# task5_eagle.net
KiCad netlist of a schematic drawn in EAGLE
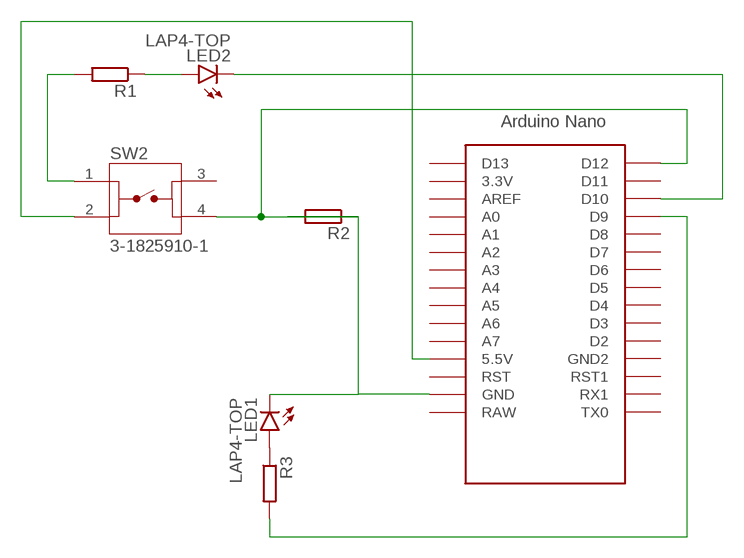
[diagram p0: schematic, sheet 1]

(export (version "E")
  (design (tool "Eeschema 10.0.6"))
  (components
    (comp (ref "LED1")
      (value "LAP4-TOP")
      (footprint "eagle-import:P47F-TOP")
      (libsource (lib "eagle-import") (part "P4-TOPLA"))
    )
    (comp (ref "LED2")
      (value "LAP4-TOP")
      (footprint "eagle-import:P47F-TOP")
      (libsource (lib "eagle-import") (part "P4-TOPLA"))
    )
    (comp (ref "R1")
      (value "R-EU_0207/12")
      (footprint "eagle-import:0207_12")
      (libsource (lib "eagle-import") (part "R-EU_0207/12"))
    )
    (comp (ref "R2")
      (value "R-EU_0207/12")
      (footprint "eagle-import:0207_12")
      (libsource (lib "eagle-import") (part "R-EU_0207/12"))
    )
    (comp (ref "R3")
      (value "R-EU_0207/12")
      (footprint "eagle-import:0207_12")
      (libsource (lib "eagle-import") (part "R-EU_0207/12"))
    )
    (comp (ref "SW2")
      (value "3-1825910-1")
      (footprint "eagle-import:TE_3-1825910-1")
      (fields (field (name "MF") "TE Connectivity"))
      (libsource (lib "eagle-import") (part "3-1825910-1"))
    )
    (comp (ref "U$1")
      (value "NANO")
      (footprint "eagle-import:NANO")
      (libsource (lib "eagle-import") (part "NANO"))
    )
  )
  (nets
    (net (code "1") (name "Net-(LED1-PadA)") (class "Default")
      (node (ref "LED1") (pin "A") (pinfunction "A_A") (pintype "passive"))
      (node (ref "R3") (pin "1") (pinfunction "1_1") (pintype "passive"))
    )
    (net (code "2") (name "Net-(LED1-PadC)") (class "Default")
      (node (ref "LED1") (pin "C") (pinfunction "C_C") (pintype "passive"))
      (node (ref "R2") (pin "1") (pinfunction "1_1") (pintype "passive"))
      (node (ref "R2") (pin "2") (pinfunction "2_2") (pintype "passive"))
      (node (ref "SW2") (pin "4") (pinfunction "4_4") (pintype "passive"))
      (node (ref "U$1") (pin "D12") (pinfunction "D12_D12") (pintype "bidirectional"))
      (node (ref "U$1") (pin "GND") (pinfunction "GND_GND") (pintype "bidirectional"))
    )
    (net (code "3") (name "Net-(LED2-PadA)") (class "Default")
      (node (ref "LED2") (pin "A") (pinfunction "A_A") (pintype "passive"))
      (node (ref "R1") (pin "1") (pinfunction "1_1") (pintype "passive"))
    )
    (net (code "4") (name "Net-(LED2-PadC)") (class "Default")
      (node (ref "LED2") (pin "C") (pinfunction "C_C") (pintype "passive"))
      (node (ref "U$1") (pin "D10") (pinfunction "D10_D10") (pintype "bidirectional"))
    )
    (net (code "5") (name "Net-(R1-Pad2)") (class "Default")
      (node (ref "R1") (pin "2") (pinfunction "2_2") (pintype "passive"))
      (node (ref "SW2") (pin "1") (pinfunction "1_1") (pintype "passive"))
    )
    (net (code "6") (name "Net-(R3-Pad2)") (class "Default")
      (node (ref "R3") (pin "2") (pinfunction "2_2") (pintype "passive"))
      (node (ref "U$1") (pin "D9") (pinfunction "D9_D9") (pintype "bidirectional"))
    )
    (net (code "7") (name "Net-(U$1-5.5V)") (class "Default")
      (node (ref "SW2") (pin "2") (pinfunction "2_2") (pintype "passive"))
      (node (ref "U$1") (pin "5V") (pinfunction "5.5V_5V") (pintype "bidirectional"))
    )
    (net (code "8") (name "unconnected-(SW2-Pad3)") (class "Default")
      (node (ref "SW2") (pin "3") (pinfunction "3_3") (pintype "passive"))
    )
    (net (code "9") (name "unconnected-(U$1-GND2-PadGND1)") (class "Default")
      (node (ref "U$1") (pin "GND1") (pinfunction "GND2_GND1") (pintype "bidirectional"))
    )
    (net (code "10") (name "unconnected-(U$1-Pad3.3V)") (class "Default")
      (node (ref "U$1") (pin "3.3V") (pinfunction "3.3V_3.3V") (pintype "bidirectional"))
    )
    (net (code "11") (name "unconnected-(U$1-PadA0)") (class "Default")
      (node (ref "U$1") (pin "A0") (pinfunction "A0_A0") (pintype "bidirectional"))
    )
    (net (code "12") (name "unconnected-(U$1-PadA1)") (class "Default")
      (node (ref "U$1") (pin "A1") (pinfunction "A1_A1") (pintype "bidirectional"))
    )
    (net (code "13") (name "unconnected-(U$1-PadA2)") (class "Default")
      (node (ref "U$1") (pin "A2") (pinfunction "A2_A2") (pintype "bidirectional"))
    )
    (net (code "14") (name "unconnected-(U$1-PadA3)") (class "Default")
      (node (ref "U$1") (pin "A3") (pinfunction "A3_A3") (pintype "bidirectional"))
    )
    (net (code "15") (name "unconnected-(U$1-PadA4)") (class "Default")
      (node (ref "U$1") (pin "A4") (pinfunction "A4_A4") (pintype "bidirectional"))
    )
    (net (code "16") (name "unconnected-(U$1-PadA5)") (class "Default")
      (node (ref "U$1") (pin "A5") (pinfunction "A5_A5") (pintype "bidirectional"))
    )
    (net (code "17") (name "unconnected-(U$1-PadA6)") (class "Default")
      (node (ref "U$1") (pin "A6") (pinfunction "A6_A6") (pintype "bidirectional"))
    )
    (net (code "18") (name "unconnected-(U$1-PadA7)") (class "Default")
      (node (ref "U$1") (pin "A7") (pinfunction "A7_A7") (pintype "bidirectional"))
    )
    (net (code "19") (name "unconnected-(U$1-PadAREF)") (class "Default")
      (node (ref "U$1") (pin "AREF") (pinfunction "AREF_AREF") (pintype "bidirectional"))
    )
    (net (code "20") (name "unconnected-(U$1-PadD2)") (class "Default")
      (node (ref "U$1") (pin "D2") (pinfunction "D2_D2") (pintype "bidirectional"))
    )
    (net (code "21") (name "unconnected-(U$1-PadD3)") (class "Default")
      (node (ref "U$1") (pin "D3") (pinfunction "D3_D3") (pintype "bidirectional"))
    )
    (net (code "22") (name "unconnected-(U$1-PadD4)") (class "Default")
      (node (ref "U$1") (pin "D4") (pinfunction "D4_D4") (pintype "bidirectional"))
    )
    (net (code "23") (name "unconnected-(U$1-PadD5)") (class "Default")
      (node (ref "U$1") (pin "D5") (pinfunction "D5_D5") (pintype "bidirectional"))
    )
    (net (code "24") (name "unconnected-(U$1-PadD6)") (class "Default")
      (node (ref "U$1") (pin "D6") (pinfunction "D6_D6") (pintype "bidirectional"))
    )
    (net (code "25") (name "unconnected-(U$1-PadD7)") (class "Default")
      (node (ref "U$1") (pin "D7") (pinfunction "D7_D7") (pintype "bidirectional"))
    )
    (net (code "26") (name "unconnected-(U$1-PadD8)") (class "Default")
      (node (ref "U$1") (pin "D8") (pinfunction "D8_D8") (pintype "bidirectional"))
    )
    (net (code "27") (name "unconnected-(U$1-PadD11)") (class "Default")
      (node (ref "U$1") (pin "D11") (pinfunction "D11_D11") (pintype "bidirectional"))
    )
    (net (code "28") (name "unconnected-(U$1-PadD13)") (class "Default")
      (node (ref "U$1") (pin "D13") (pinfunction "D13_D13") (pintype "bidirectional"))
    )
    (net (code "29") (name "unconnected-(U$1-PadICSP1)") (class "Default")
      (node (ref "U$1") (pin "ICSP1") (pinfunction "ICSP1_ICSP1") (pintype "bidirectional"))
    )
    (net (code "30") (name "unconnected-(U$1-PadICSP2)") (class "Default")
      (node (ref "U$1") (pin "ICSP2") (pinfunction "ICSP2_ICSP2") (pintype "bidirectional"))
    )
    (net (code "31") (name "unconnected-(U$1-PadICSP3)") (class "Default")
      (node (ref "U$1") (pin "ICSP3") (pinfunction "ICSP3_ICSP3") (pintype "bidirectional"))
    )
    (net (code "32") (name "unconnected-(U$1-PadICSP4)") (class "Default")
      (node (ref "U$1") (pin "ICSP4") (pinfunction "ICSP4_ICSP4") (pintype "bidirectional"))
    )
    (net (code "33") (name "unconnected-(U$1-PadICSP5)") (class "Default")
      (node (ref "U$1") (pin "ICSP5") (pinfunction "ICSP5_ICSP5") (pintype "bidirectional"))
    )
    (net (code "34") (name "unconnected-(U$1-PadICSP6)") (class "Default")
      (node (ref "U$1") (pin "ICSP6") (pinfunction "ICSP6_ICSP6") (pintype "bidirectional"))
    )
    (net (code "35") (name "unconnected-(U$1-PadRAW)") (class "Default")
      (node (ref "U$1") (pin "RAW") (pinfunction "RAW_RAW") (pintype "bidirectional"))
    )
    (net (code "36") (name "unconnected-(U$1-PadRST)") (class "Default")
      (node (ref "U$1") (pin "RST") (pinfunction "RST_RST") (pintype "bidirectional"))
    )
    (net (code "37") (name "unconnected-(U$1-PadRST1)") (class "Default")
      (node (ref "U$1") (pin "RST1") (pinfunction "RST1_RST1") (pintype "bidirectional"))
    )
    (net (code "38") (name "unconnected-(U$1-PadRX1)") (class "Default")
      (node (ref "U$1") (pin "RX1") (pinfunction "RX1_RX1") (pintype "bidirectional"))
    )
    (net (code "39") (name "unconnected-(U$1-PadTX0)") (class "Default")
      (node (ref "U$1") (pin "TX0") (pinfunction "TX0_TX0") (pintype "bidirectional"))
    )
  )
)
